# Smart-LCD_1V0.net
KiCad netlist of a schematic drawn in EAGLE
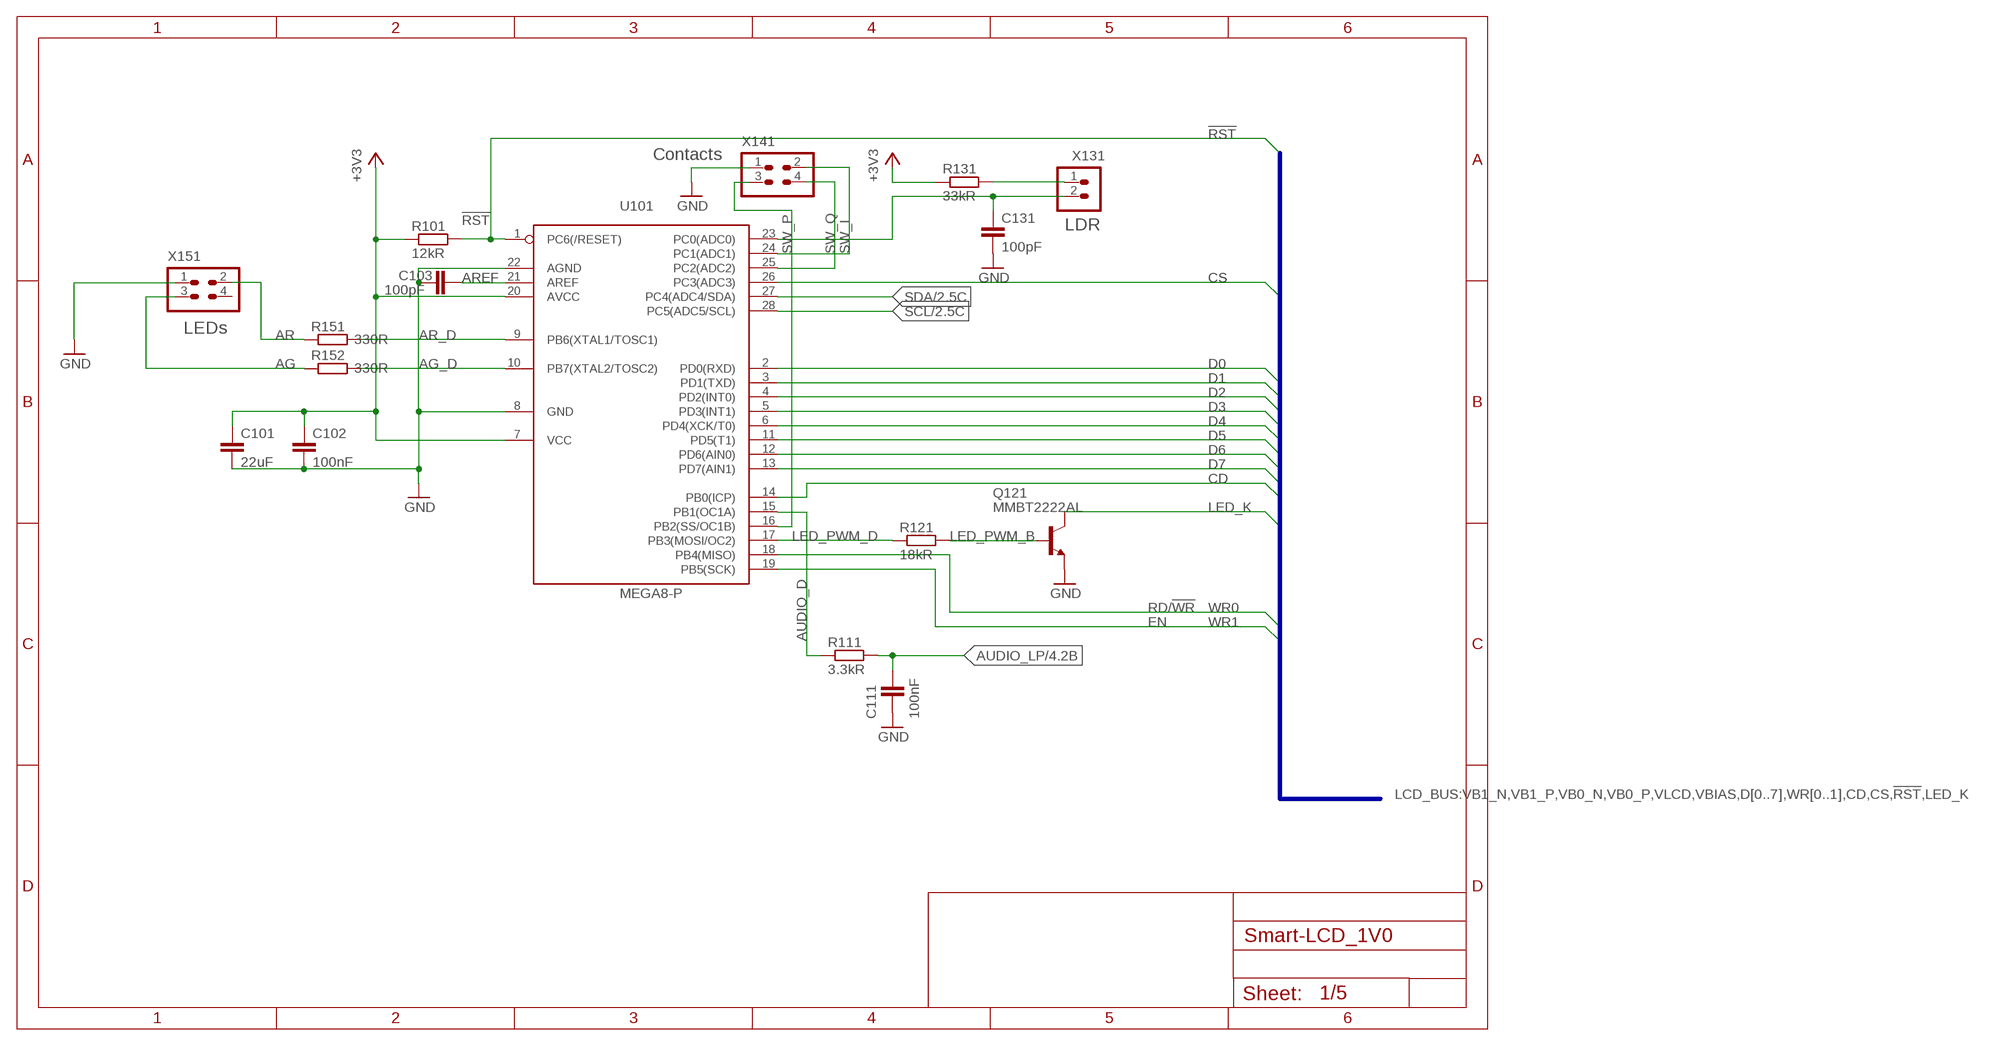
[diagram p0: schematic, sheet 1]
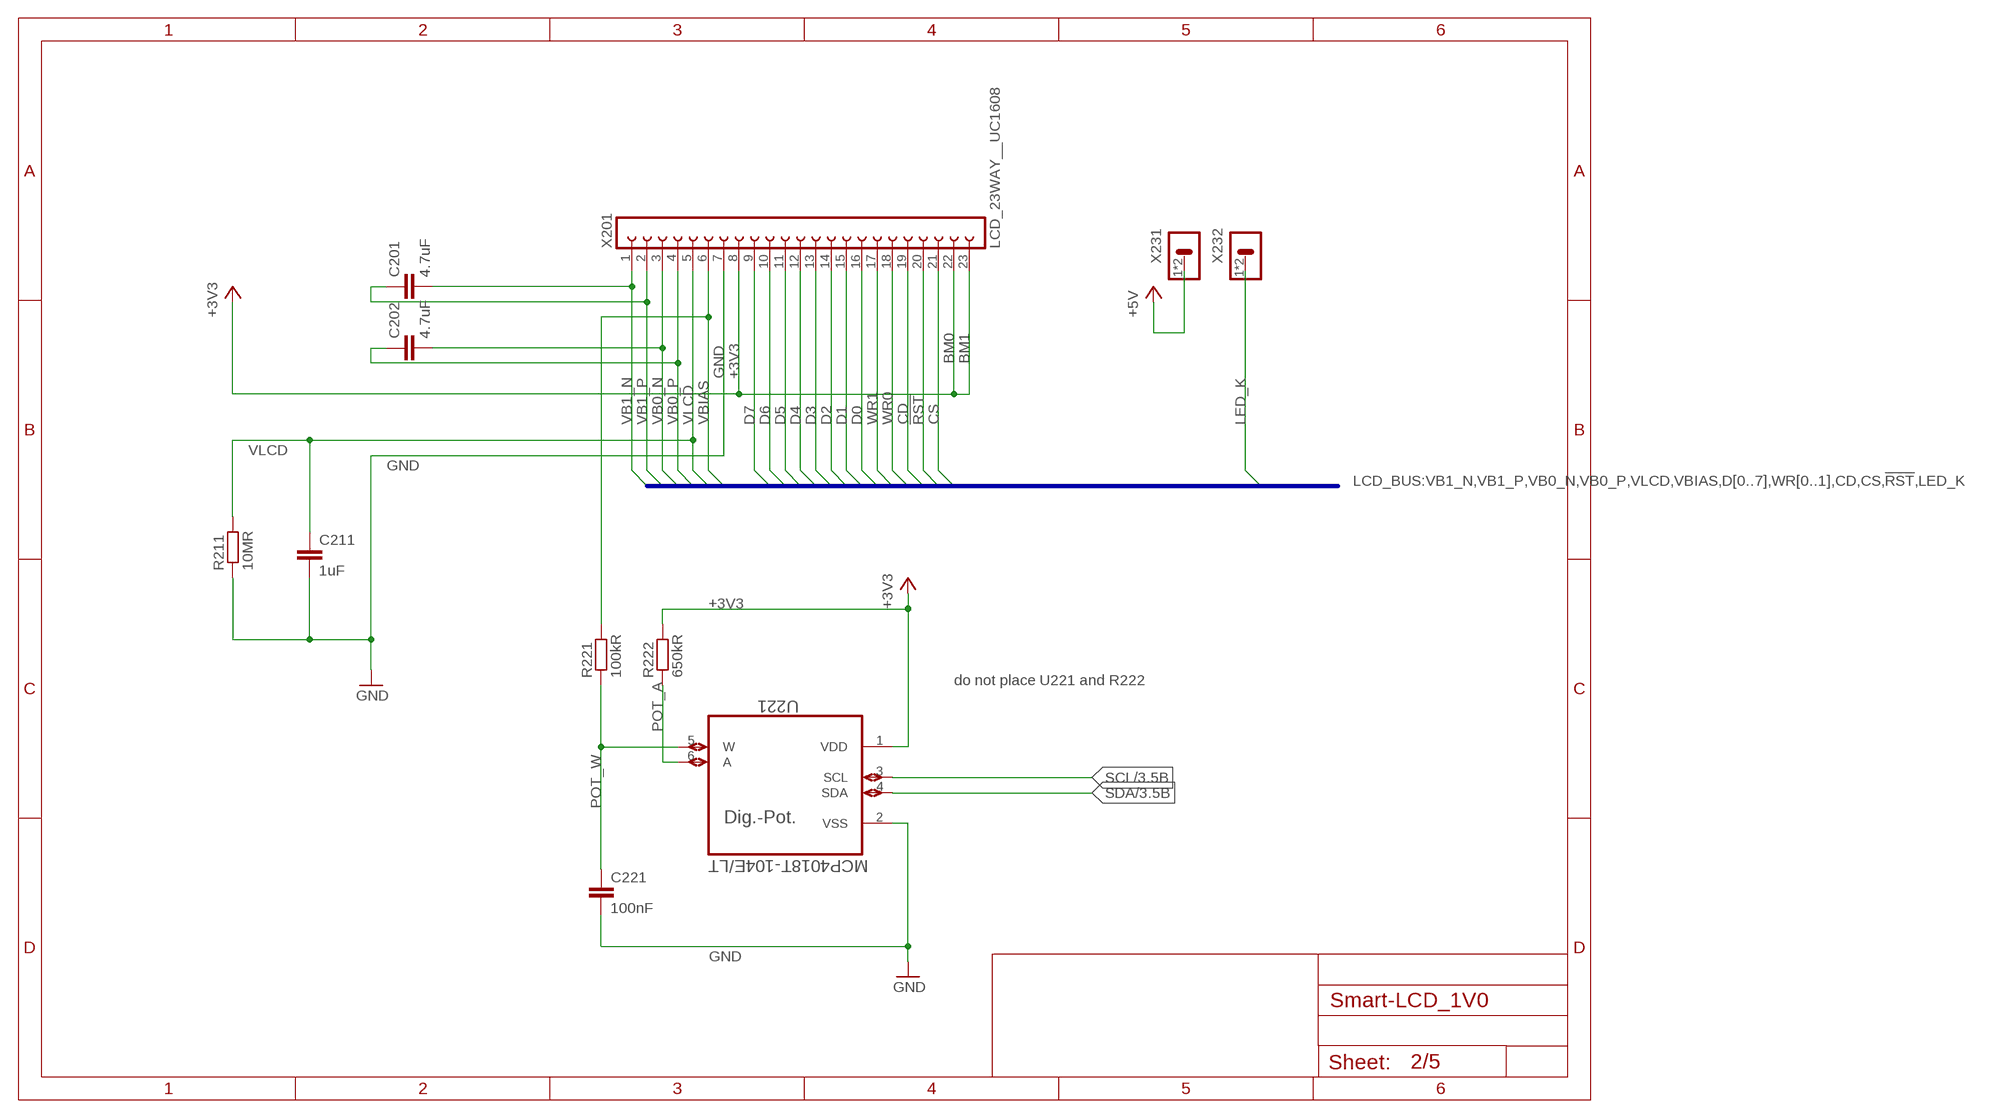
[diagram p1: schematic, sheet 2]
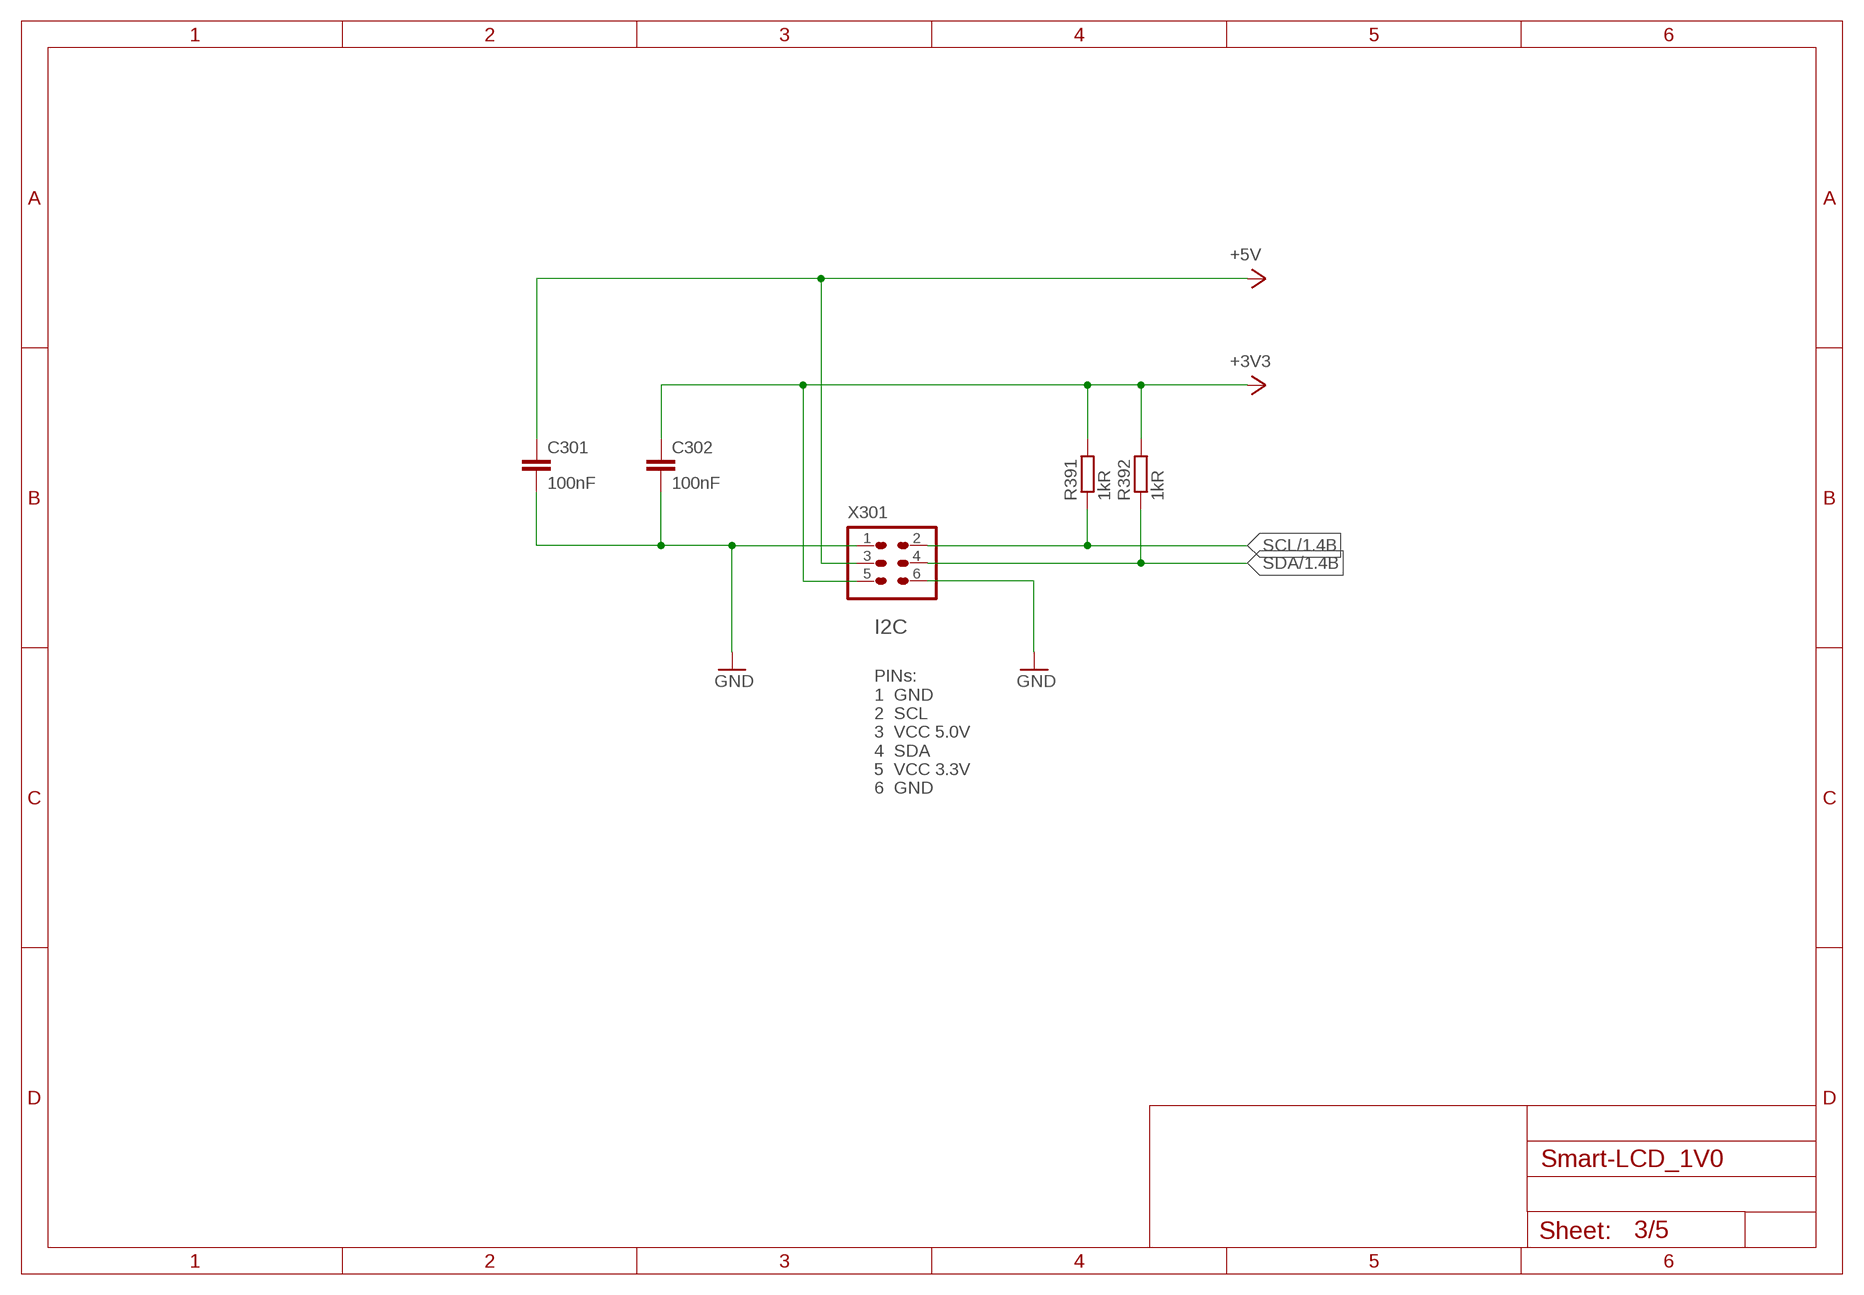
[diagram p2: schematic, sheet 3]
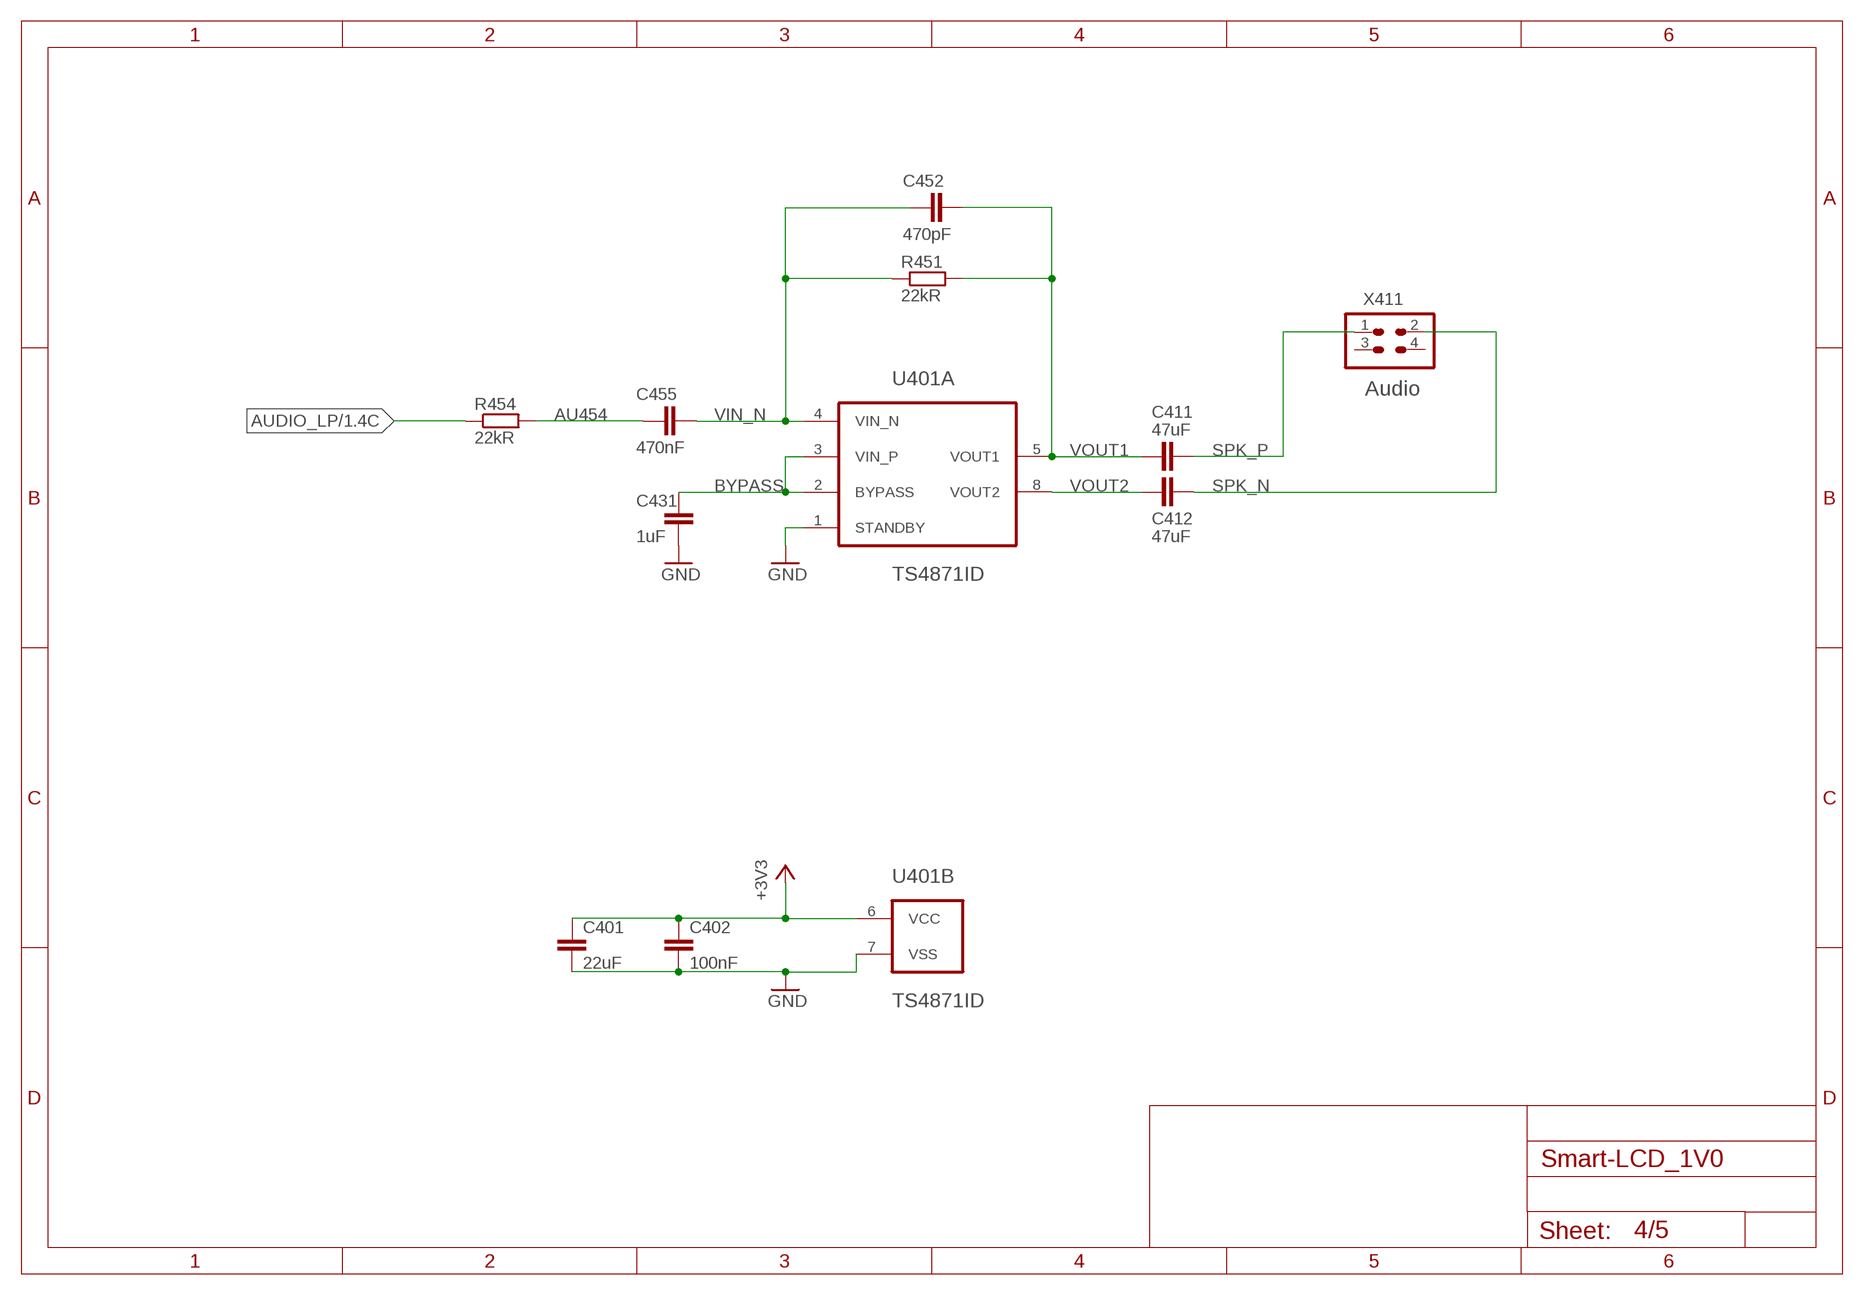
[diagram p3: schematic, sheet 4]
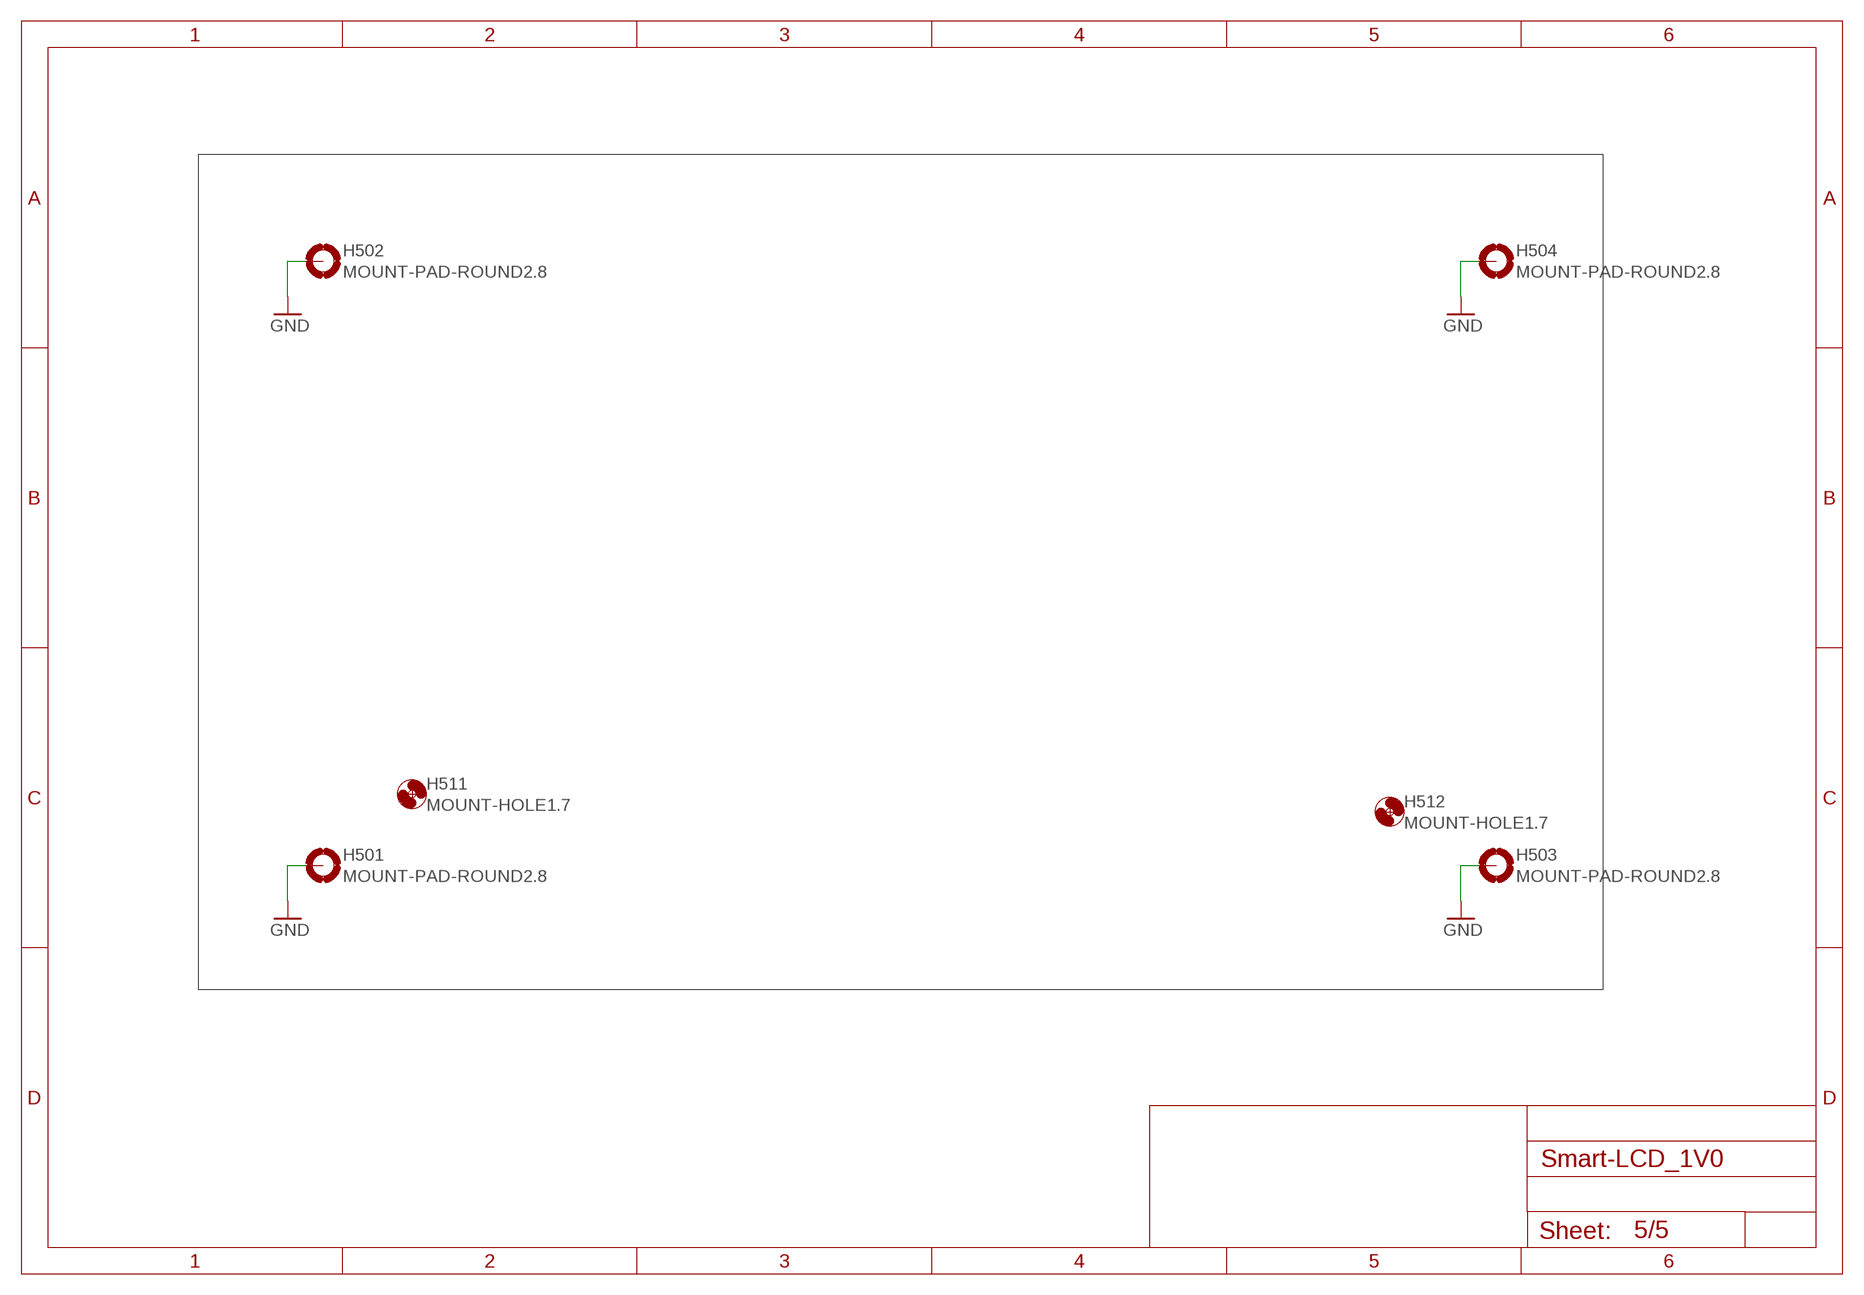
[diagram p4: schematic, sheet 5]

(export (version "E")
  (design (tool "Eeschema 10.0.6"))
  (components
    (comp (ref "C301")
      (value "100nF")
      (footprint "eagle-import:C0805")
      (libsource (lib "eagle-import") (part "C-EUC0805"))
    )
    (comp (ref "C302")
      (value "100nF")
      (footprint "eagle-import:C0805")
      (libsource (lib "eagle-import") (part "C-EUC0805"))
    )
    (comp (ref "R391")
      (value "1kR")
      (footprint "eagle-import:R0603")
      (libsource (lib "eagle-import") (part "R-EU_R0603"))
    )
    (comp (ref "R392")
      (value "1kR")
      (footprint "eagle-import:R0603")
      (libsource (lib "eagle-import") (part "R-EU_R0603"))
    )
    (comp (ref "X301")
      (value "I2C")
      (footprint "eagle-import:2X03")
      (libsource (lib "eagle-import") (part "HEADER-2X3"))
    )
    (comp (ref "C101")
      (value "22uF")
      (footprint "eagle-import:C0805")
      (libsource (lib "eagle-import") (part "C-EUC0805"))
    )
    (comp (ref "C102")
      (value "100nF")
      (footprint "eagle-import:C0805")
      (libsource (lib "eagle-import") (part "C-EUC0805"))
    )
    (comp (ref "C103")
      (value "100pF")
      (footprint "eagle-import:C0805")
      (libsource (lib "eagle-import") (part "C-EUC0805"))
    )
    (comp (ref "C111")
      (value "100nF")
      (footprint "eagle-import:C0805")
      (libsource (lib "eagle-import") (part "C-EUC0805"))
    )
    (comp (ref "C131")
      (value "100pF")
      (footprint "eagle-import:C0805")
      (libsource (lib "eagle-import") (part "C-EUC0805"))
    )
    (comp (ref "Q121")
      (value "MMBT2222AL")
      (footprint "eagle-import:SOT23")
      (libsource (lib "eagle-import") (part "MMBT2222AL"))
    )
    (comp (ref "R101")
      (value "12kR")
      (footprint "eagle-import:R0805")
      (libsource (lib "eagle-import") (part "R-EU_R0805"))
    )
    (comp (ref "R111")
      (value "3.3kR")
      (footprint "eagle-import:R0805")
      (libsource (lib "eagle-import") (part "R-EU_R0805"))
    )
    (comp (ref "R121")
      (value "18kR")
      (footprint "eagle-import:R0805")
      (libsource (lib "eagle-import") (part "R-EU_R0805"))
    )
    (comp (ref "R131")
      (value "33kR")
      (footprint "eagle-import:R0805")
      (libsource (lib "eagle-import") (part "R-EU_R0805"))
    )
    (comp (ref "R151")
      (value "330R")
      (footprint "eagle-import:R0805")
      (libsource (lib "eagle-import") (part "R-EU_R0805"))
    )
    (comp (ref "R152")
      (value "330R")
      (footprint "eagle-import:R0805")
      (libsource (lib "eagle-import") (part "R-EU_R0805"))
    )
    (comp (ref "U101")
      (value "MEGA8-P")
      (footprint "eagle-import:DIL28-3")
      (libsource (lib "eagle-import") (part "MEGA8-P"))
    )
    (comp (ref "X131")
      (value "LDR")
      (footprint "eagle-import:1X02")
      (libsource (lib "eagle-import") (part "HEADER-1X2"))
    )
    (comp (ref "X141")
      (value "Switches")
      (footprint "eagle-import:2X02")
      (libsource (lib "eagle-import") (part "HEADER-2X2"))
    )
    (comp (ref "X151")
      (value "LEDs")
      (footprint "eagle-import:2X02")
      (libsource (lib "eagle-import") (part "HEADER-2X2"))
    )
    (comp (ref "C401")
      (value "22uF")
      (footprint "eagle-import:C0805")
      (libsource (lib "eagle-import") (part "C-EUC0805"))
    )
    (comp (ref "C402")
      (value "100nF")
      (footprint "eagle-import:C0805")
      (libsource (lib "eagle-import") (part "C-EUC0805"))
    )
    (comp (ref "C411")
      (value "47uF")
      (footprint "eagle-import:C0805")
      (libsource (lib "eagle-import") (part "C-EUC0805"))
    )
    (comp (ref "C412")
      (value "47uF")
      (footprint "eagle-import:C0805")
      (libsource (lib "eagle-import") (part "C-EUC0805"))
    )
    (comp (ref "C431")
      (value "1uF")
      (footprint "eagle-import:C0805")
      (libsource (lib "eagle-import") (part "C-EUC0805"))
    )
    (comp (ref "C452")
      (value "470pF")
      (footprint "eagle-import:C0805")
      (libsource (lib "eagle-import") (part "C-EUC0805"))
    )
    (comp (ref "C455")
      (value "470nF")
      (footprint "eagle-import:C0805")
      (libsource (lib "eagle-import") (part "C-EUC0805"))
    )
    (comp (ref "R451")
      (value "22kR")
      (footprint "eagle-import:R0805")
      (libsource (lib "eagle-import") (part "R-EU_R0805"))
    )
    (comp (ref "R454")
      (value "22kR")
      (footprint "eagle-import:R0805")
      (libsource (lib "eagle-import") (part "R-EU_R0805"))
    )
    (comp (ref "U401")
      (value "TS4871ID")
      (footprint "eagle-import:SO08")
      (libsource (lib "eagle-import") (part "TS4871ID"))
    )
    (comp (ref "X411")
      (value "Audio")
      (footprint "eagle-import:2X02")
      (libsource (lib "eagle-import") (part "HEADER-2X2"))
    )
    (comp (ref "H501")
      (value "MOUNT-PAD-ROUND2.8")
      (footprint "eagle-import:2,8-PAD")
      (libsource (lib "eagle-import") (part "MOUNT-PAD-ROUND2.8"))
    )
    (comp (ref "H502")
      (value "MOUNT-PAD-ROUND2.8")
      (footprint "eagle-import:2,8-PAD")
      (libsource (lib "eagle-import") (part "MOUNT-PAD-ROUND2.8"))
    )
    (comp (ref "H503")
      (value "MOUNT-PAD-ROUND2.8")
      (footprint "eagle-import:2,8-PAD")
      (libsource (lib "eagle-import") (part "MOUNT-PAD-ROUND2.8"))
    )
    (comp (ref "H504")
      (value "MOUNT-PAD-ROUND2.8")
      (footprint "eagle-import:2,8-PAD")
      (libsource (lib "eagle-import") (part "MOUNT-PAD-ROUND2.8"))
    )
    (comp (ref "H511")
      (value "MOUNT-HOLE1.7")
      (footprint "eagle-import:1,7")
      (libsource (lib "eagle-import") (part "MOUNT-HOLE1.7"))
    )
    (comp (ref "H512")
      (value "MOUNT-HOLE1.7")
      (footprint "eagle-import:1,7")
      (libsource (lib "eagle-import") (part "MOUNT-HOLE1.7"))
    )
    (comp (ref "C201")
      (value "4.7uF")
      (footprint "eagle-import:C0805")
      (libsource (lib "eagle-import") (part "C-EUC0805"))
    )
    (comp (ref "C202")
      (value "4.7uF")
      (footprint "eagle-import:C0805")
      (libsource (lib "eagle-import") (part "C-EUC0805"))
    )
    (comp (ref "C211")
      (value "1uF")
      (footprint "eagle-import:C0805")
      (libsource (lib "eagle-import") (part "C-EUC0805"))
    )
    (comp (ref "C221")
      (value "100nF")
      (footprint "eagle-import:C0805")
      (libsource (lib "eagle-import") (part "C-EUC0805"))
    )
    (comp (ref "R211")
      (value "10MR")
      (footprint "eagle-import:R0805")
      (libsource (lib "eagle-import") (part "R-EU_R0805"))
    )
    (comp (ref "R221")
      (value "100kR")
      (footprint "eagle-import:R0805")
      (libsource (lib "eagle-import") (part "R-EU_R0805"))
    )
    (comp (ref "R222")
      (value "650kR")
      (footprint "eagle-import:R0805")
      (libsource (lib "eagle-import") (part "R-EU_R0805"))
    )
    (comp (ref "U221")
      (value "MCP4018T-104E/LT")
      (footprint "eagle-import:SOT65P210X110-6N")
      (libsource (lib "eagle-import") (part "MCP4018T-104E/LT"))
    )
    (comp (ref "X201")
      (value "LCD_23WAY__UC1608")
      (footprint "eagle-import:23X01_1MM27__UC1608")
      (libsource (lib "eagle-import") (part "LCD_23WAY__UC1608"))
    )
    (comp (ref "X231")
      (value "LED_A")
      (footprint "eagle-import:P1-20X0.80")
      (libsource (lib "eagle-import") (part "CON_1X"))
    )
    (comp (ref "X232")
      (value "LED_K")
      (footprint "eagle-import:P1-20X0.80")
      (libsource (lib "eagle-import") (part "CON_1X"))
    )
  )
  (nets
    (net (code "8") (name "+3V3") (class "Default")
      (node (ref "C101") (pin "1") (pinfunction "1_1") (pintype "passive"))
      (node (ref "C102") (pin "1") (pinfunction "1_1") (pintype "passive"))
      (node (ref "C302") (pin "1") (pinfunction "1_1") (pintype "passive"))
      (node (ref "C401") (pin "1") (pinfunction "1_1") (pintype "passive"))
      (node (ref "C402") (pin "1") (pinfunction "1_1") (pintype "passive"))
      (node (ref "R101") (pin "1") (pinfunction "1_1") (pintype "passive"))
      (node (ref "R131") (pin "1") (pinfunction "1_1") (pintype "passive"))
      (node (ref "R222") (pin "2") (pinfunction "2_2") (pintype "passive"))
      (node (ref "R391") (pin "2") (pinfunction "2_2") (pintype "passive"))
      (node (ref "R392") (pin "2") (pinfunction "2_2") (pintype "passive"))
      (node (ref "U101") (pin "20") (pinfunction "AVCC_20") (pintype "bidirectional"))
      (node (ref "U101") (pin "7") (pinfunction "VCC_7") (pintype "bidirectional"))
      (node (ref "U221") (pin "1") (pinfunction "VDD_1") (pintype "power_in"))
      (node (ref "U401") (pin "6") (pinfunction "VCC_6") (pintype "power_in"))
      (node (ref "X201") (pin "22") (pinfunction "22_22") (pintype "passive"))
      (node (ref "X201") (pin "23") (pinfunction "23_23") (pintype "passive"))
      (node (ref "X201") (pin "8") (pinfunction "8_8") (pintype "passive"))
      (node (ref "X301") (pin "5") (pinfunction "5_5") (pintype "passive"))
    )
    (net (code "9") (name "+5V") (class "Default")
      (node (ref "C301") (pin "1") (pinfunction "1_1") (pintype "passive"))
      (node (ref "X231") (pin "1") (pinfunction "1_1") (pintype "passive"))
      (node (ref "X231") (pin "2") (pinfunction "1_2") (pintype "passive"))
      (node (ref "X301") (pin "3") (pinfunction "3_3") (pintype "passive"))
    )
    (net (code "12") (name "AG") (class "Default")
      (node (ref "R152") (pin "1") (pinfunction "1_1") (pintype "passive"))
      (node (ref "X151") (pin "3") (pinfunction "3_3") (pintype "passive"))
    )
    (net (code "13") (name "AG_D") (class "Default")
      (node (ref "R152") (pin "2") (pinfunction "2_2") (pintype "passive"))
      (node (ref "U101") (pin "10") (pinfunction "PB7(XTAL2/TOSC2)_10") (pintype "bidirectional"))
    )
    (net (code "14") (name "AR") (class "Default")
      (node (ref "R151") (pin "1") (pinfunction "1_1") (pintype "passive"))
      (node (ref "X151") (pin "2") (pinfunction "2_2") (pintype "passive"))
    )
    (net (code "15") (name "AREF") (class "Default")
      (node (ref "C103") (pin "2") (pinfunction "2_2") (pintype "passive"))
      (node (ref "U101") (pin "21") (pinfunction "AREF_21") (pintype "bidirectional"))
    )
    (net (code "16") (name "AR_D") (class "Default")
      (node (ref "R151") (pin "2") (pinfunction "2_2") (pintype "passive"))
      (node (ref "U101") (pin "9") (pinfunction "PB6(XTAL1/TOSC1)_9") (pintype "bidirectional"))
    )
    (net (code "17") (name "AU454") (class "Default")
      (node (ref "C455") (pin "1") (pinfunction "1_1") (pintype "passive"))
      (node (ref "R454") (pin "2") (pinfunction "2_2") (pintype "passive"))
    )
    (net (code "18") (name "AUDIO_D") (class "Default")
      (node (ref "R111") (pin "1") (pinfunction "1_1") (pintype "passive"))
      (node (ref "U101") (pin "15") (pinfunction "PB1(OC1A)_15") (pintype "bidirectional"))
    )
    (net (code "19") (name "AUDIO_LP") (class "Default")
      (node (ref "C111") (pin "1") (pinfunction "1_1") (pintype "passive"))
      (node (ref "R111") (pin "2") (pinfunction "2_2") (pintype "passive"))
      (node (ref "R454") (pin "1") (pinfunction "1_1") (pintype "passive"))
    )
    (net (code "20") (name "BYPASS") (class "Default")
      (node (ref "C431") (pin "1") (pinfunction "1_1") (pintype "passive"))
      (node (ref "U401") (pin "2") (pinfunction "BYPASS_2") (pintype "passive"))
      (node (ref "U401") (pin "3") (pinfunction "VIN_P_3") (pintype "passive"))
    )
    (net (code "21") (name "CD") (class "Default")
      (node (ref "U101") (pin "14") (pinfunction "PB0(ICP)_14") (pintype "bidirectional"))
      (node (ref "X201") (pin "19") (pinfunction "19_19") (pintype "passive"))
    )
    (net (code "22") (name "CS") (class "Default")
      (node (ref "U101") (pin "26") (pinfunction "PC3(ADC3)_26") (pintype "bidirectional"))
      (node (ref "X201") (pin "21") (pinfunction "21_21") (pintype "passive"))
    )
    (net (code "23") (name "D0") (class "Default")
      (node (ref "U101") (pin "2") (pinfunction "PD0(RXD)_2") (pintype "bidirectional"))
      (node (ref "X201") (pin "16") (pinfunction "16_16") (pintype "passive"))
    )
    (net (code "24") (name "D1") (class "Default")
      (node (ref "U101") (pin "3") (pinfunction "PD1(TXD)_3") (pintype "bidirectional"))
      (node (ref "X201") (pin "15") (pinfunction "15_15") (pintype "passive"))
    )
    (net (code "25") (name "D2") (class "Default")
      (node (ref "U101") (pin "4") (pinfunction "PD2(INT0)_4") (pintype "bidirectional"))
      (node (ref "X201") (pin "14") (pinfunction "14_14") (pintype "passive"))
    )
    (net (code "26") (name "D3") (class "Default")
      (node (ref "U101") (pin "5") (pinfunction "PD3(INT1)_5") (pintype "bidirectional"))
      (node (ref "X201") (pin "13") (pinfunction "13_13") (pintype "passive"))
    )
    (net (code "27") (name "D4") (class "Default")
      (node (ref "U101") (pin "6") (pinfunction "PD4(XCK/T0)_6") (pintype "bidirectional"))
      (node (ref "X201") (pin "12") (pinfunction "12_12") (pintype "passive"))
    )
    (net (code "28") (name "D5") (class "Default")
      (node (ref "U101") (pin "11") (pinfunction "PD5(T1)_11") (pintype "bidirectional"))
      (node (ref "X201") (pin "11") (pinfunction "11_11") (pintype "passive"))
    )
    (net (code "29") (name "D6") (class "Default")
      (node (ref "U101") (pin "12") (pinfunction "PD6(AIN0)_12") (pintype "bidirectional"))
      (node (ref "X201") (pin "10") (pinfunction "10_10") (pintype "passive"))
    )
    (net (code "30") (name "D7") (class "Default")
      (node (ref "U101") (pin "13") (pinfunction "PD7(AIN1)_13") (pintype "bidirectional"))
      (node (ref "X201") (pin "9") (pinfunction "9_9") (pintype "passive"))
    )
    (net (code "31") (name "GND") (class "Default")
      (node (ref "C101") (pin "2") (pinfunction "2_2") (pintype "passive"))
      (node (ref "C102") (pin "2") (pinfunction "2_2") (pintype "passive"))
      (node (ref "C103") (pin "1") (pinfunction "1_1") (pintype "passive"))
      (node (ref "C111") (pin "2") (pinfunction "2_2") (pintype "passive"))
      (node (ref "C131") (pin "2") (pinfunction "2_2") (pintype "passive"))
      (node (ref "C211") (pin "2") (pinfunction "2_2") (pintype "passive"))
      (node (ref "C221") (pin "2") (pinfunction "2_2") (pintype "passive"))
      (node (ref "C301") (pin "2") (pinfunction "2_2") (pintype "passive"))
      (node (ref "C302") (pin "2") (pinfunction "2_2") (pintype "passive"))
      (node (ref "C401") (pin "2") (pinfunction "2_2") (pintype "passive"))
      (node (ref "C402") (pin "2") (pinfunction "2_2") (pintype "passive"))
      (node (ref "C431") (pin "2") (pinfunction "2_2") (pintype "passive"))
      (node (ref "H501") (pin "B2,8") (pinfunction "MOUNT_B2,8") (pintype "passive"))
      (node (ref "H502") (pin "B2,8") (pinfunction "MOUNT_B2,8") (pintype "passive"))
      (node (ref "H503") (pin "B2,8") (pinfunction "MOUNT_B2,8") (pintype "passive"))
      (node (ref "H504") (pin "B2,8") (pinfunction "MOUNT_B2,8") (pintype "passive"))
      (node (ref "Q121") (pin "2") (pinfunction "E_2") (pintype "passive"))
      (node (ref "R211") (pin "1") (pinfunction "1_1") (pintype "passive"))
      (node (ref "U101") (pin "22") (pinfunction "AGND_22") (pintype "bidirectional"))
      (node (ref "U101") (pin "8") (pinfunction "GND_8") (pintype "bidirectional"))
      (node (ref "U221") (pin "2") (pinfunction "VSS_2") (pintype "power_in"))
      (node (ref "U401") (pin "1") (pinfunction "STANDBY_1") (pintype "input"))
      (node (ref "U401") (pin "7") (pinfunction "VSS_7") (pintype "power_in"))
      (node (ref "X141") (pin "1") (pinfunction "1_1") (pintype "passive"))
      (node (ref "X151") (pin "1") (pinfunction "1_1") (pintype "passive"))
      (node (ref "X201") (pin "7") (pinfunction "7_7") (pintype "passive"))
      (node (ref "X301") (pin "1") (pinfunction "1_1") (pintype "passive"))
      (node (ref "X301") (pin "6") (pinfunction "6_6") (pintype "passive"))
    )
    (net (code "32") (name "LED_K") (class "Default")
      (node (ref "Q121") (pin "3") (pinfunction "C_3") (pintype "passive"))
      (node (ref "X232") (pin "1") (pinfunction "1_1") (pintype "passive"))
      (node (ref "X232") (pin "2") (pinfunction "1_2") (pintype "passive"))
    )
    (net (code "33") (name "LED_PWM_B") (class "Default")
      (node (ref "Q121") (pin "1") (pinfunction "B_1") (pintype "passive"))
      (node (ref "R121") (pin "2") (pinfunction "2_2") (pintype "passive"))
    )
    (net (code "34") (name "LED_PWM_D") (class "Default")
      (node (ref "R121") (pin "1") (pinfunction "1_1") (pintype "passive"))
      (node (ref "U101") (pin "17") (pinfunction "PB3(MOSI/OC2)_17") (pintype "bidirectional"))
    )
    (net (code "35") (name "Net-(R131-Pad2)") (class "Default")
      (node (ref "R131") (pin "2") (pinfunction "2_2") (pintype "passive"))
      (node (ref "X131") (pin "1") (pinfunction "1_1") (pintype "passive"))
    )
    (net (code "36") (name "Net-(U101-PC0(ADC0))") (class "Default")
      (node (ref "C131") (pin "1") (pinfunction "1_1") (pintype "passive"))
      (node (ref "U101") (pin "23") (pinfunction "PC0(ADC0)_23") (pintype "bidirectional"))
      (node (ref "X131") (pin "2") (pinfunction "2_2") (pintype "passive"))
    )
    (net (code "37") (name "POT_A") (class "Default")
      (node (ref "R222") (pin "1") (pinfunction "1_1") (pintype "passive"))
      (node (ref "U221") (pin "6") (pinfunction "A_6") (pintype "bidirectional"))
    )
    (net (code "38") (name "POT_W") (class "Default")
      (node (ref "C221") (pin "1") (pinfunction "1_1") (pintype "passive"))
      (node (ref "R221") (pin "1") (pinfunction "1_1") (pintype "passive"))
      (node (ref "U221") (pin "5") (pinfunction "W_5") (pintype "bidirectional"))
    )
    (net (code "39") (name "SCL") (class "Default")
      (node (ref "R391") (pin "1") (pinfunction "1_1") (pintype "passive"))
      (node (ref "U101") (pin "28") (pinfunction "PC5(ADC5/SCL)_28") (pintype "bidirectional"))
      (node (ref "U221") (pin "3") (pinfunction "SCL_3") (pintype "bidirectional"))
      (node (ref "X301") (pin "2") (pinfunction "2_2") (pintype "passive"))
    )
    (net (code "40") (name "SDA") (class "Default")
      (node (ref "R392") (pin "1") (pinfunction "1_1") (pintype "passive"))
      (node (ref "U101") (pin "27") (pinfunction "PC4(ADC4/SDA)_27") (pintype "bidirectional"))
      (node (ref "U221") (pin "4") (pinfunction "SDA_4") (pintype "bidirectional"))
      (node (ref "X301") (pin "4") (pinfunction "4_4") (pintype "passive"))
    )
    (net (code "41") (name "SPK_N") (class "Default")
      (node (ref "C412") (pin "2") (pinfunction "2_2") (pintype "passive"))
      (node (ref "X411") (pin "2") (pinfunction "2_2") (pintype "passive"))
    )
    (net (code "42") (name "SPK_P") (class "Default")
      (node (ref "C411") (pin "2") (pinfunction "2_2") (pintype "passive"))
      (node (ref "X411") (pin "1") (pinfunction "1_1") (pintype "passive"))
    )
    (net (code "43") (name "SW_I") (class "Default")
      (node (ref "U101") (pin "24") (pinfunction "PC1(ADC1)_24") (pintype "bidirectional"))
      (node (ref "X141") (pin "2") (pinfunction "2_2") (pintype "passive"))
    )
    (net (code "44") (name "SW_P") (class "Default")
      (node (ref "U101") (pin "16") (pinfunction "PB2(SS/OC1B)_16") (pintype "bidirectional"))
      (node (ref "X141") (pin "3") (pinfunction "3_3") (pintype "passive"))
    )
    (net (code "45") (name "SW_Q") (class "Default")
      (node (ref "U101") (pin "25") (pinfunction "PC2(ADC2)_25") (pintype "bidirectional"))
      (node (ref "X141") (pin "4") (pinfunction "4_4") (pintype "passive"))
    )
    (net (code "46") (name "VB0_N") (class "Default")
      (node (ref "C202") (pin "2") (pinfunction "2_2") (pintype "passive"))
      (node (ref "X201") (pin "3") (pinfunction "3_3") (pintype "passive"))
    )
    (net (code "47") (name "VB0_P") (class "Default")
      (node (ref "C202") (pin "1") (pinfunction "1_1") (pintype "passive"))
      (node (ref "X201") (pin "4") (pinfunction "4_4") (pintype "passive"))
    )
    (net (code "48") (name "VB1_N") (class "Default")
      (node (ref "C201") (pin "2") (pinfunction "2_2") (pintype "passive"))
      (node (ref "X201") (pin "1") (pinfunction "1_1") (pintype "passive"))
    )
    (net (code "49") (name "VB1_P") (class "Default")
      (node (ref "C201") (pin "1") (pinfunction "1_1") (pintype "passive"))
      (node (ref "X201") (pin "2") (pinfunction "2_2") (pintype "passive"))
    )
    (net (code "50") (name "VBIAS") (class "Default")
      (node (ref "R221") (pin "2") (pinfunction "2_2") (pintype "passive"))
      (node (ref "X201") (pin "6") (pinfunction "6_6") (pintype "passive"))
    )
    (net (code "51") (name "VIN_N") (class "Default")
      (node (ref "C452") (pin "1") (pinfunction "1_1") (pintype "passive"))
      (node (ref "C455") (pin "2") (pinfunction "2_2") (pintype "passive"))
      (node (ref "R451") (pin "1") (pinfunction "1_1") (pintype "passive"))
      (node (ref "U401") (pin "4") (pinfunction "VIN_N_4") (pintype "passive"))
    )
    (net (code "52") (name "VLCD") (class "Default")
      (node (ref "C211") (pin "1") (pinfunction "1_1") (pintype "passive"))
      (node (ref "R211") (pin "2") (pinfunction "2_2") (pintype "passive"))
      (node (ref "X201") (pin "5") (pinfunction "5_5") (pintype "passive"))
    )
    (net (code "53") (name "VOUT1") (class "Default")
      (node (ref "C411") (pin "1") (pinfunction "1_1") (pintype "passive"))
      (node (ref "C452") (pin "2") (pinfunction "2_2") (pintype "passive"))
      (node (ref "R451") (pin "2") (pinfunction "2_2") (pintype "passive"))
      (node (ref "U401") (pin "5") (pinfunction "VOUT1_5") (pintype "passive"))
    )
    (net (code "54") (name "VOUT2") (class "Default")
      (node (ref "C412") (pin "1") (pinfunction "1_1") (pintype "passive"))
      (node (ref "U401") (pin "8") (pinfunction "VOUT2_8") (pintype "passive"))
    )
    (net (code "55") (name "WR0") (class "Default")
      (node (ref "U101") (pin "18") (pinfunction "PB4(MISO)_18") (pintype "bidirectional"))
      (node (ref "X201") (pin "18") (pinfunction "18_18") (pintype "passive"))
    )
    (net (code "56") (name "WR1") (class "Default")
      (node (ref "U101") (pin "19") (pinfunction "PB5(SCK)_19") (pintype "bidirectional"))
      (node (ref "X201") (pin "17") (pinfunction "17_17") (pintype "passive"))
    )
    (net (code "57") (name "unconnected-(X151-Pad4)") (class "Default")
      (node (ref "X151") (pin "4") (pinfunction "4_4") (pintype "passive"))
    )
    (net (code "58") (name "unconnected-(X411-Pad3)") (class "Default")
      (node (ref "X411") (pin "3") (pinfunction "3_3") (pintype "passive"))
    )
    (net (code "59") (name "unconnected-(X411-Pad4)") (class "Default")
      (node (ref "X411") (pin "4") (pinfunction "4_4") (pintype "passive"))
    )
    (net (code "60") (name "~{RST}") (class "Default")
      (node (ref "R101") (pin "2") (pinfunction "2_2") (pintype "passive"))
      (node (ref "U101") (pin "1") (pinfunction "PC6(/RESET)_1") (pintype "bidirectional"))
      (node (ref "X201") (pin "20") (pinfunction "20_20") (pintype "passive"))
    )
  )
)
